# Supply__1.net
KiCad netlist of a schematic drawn in Altium Designer
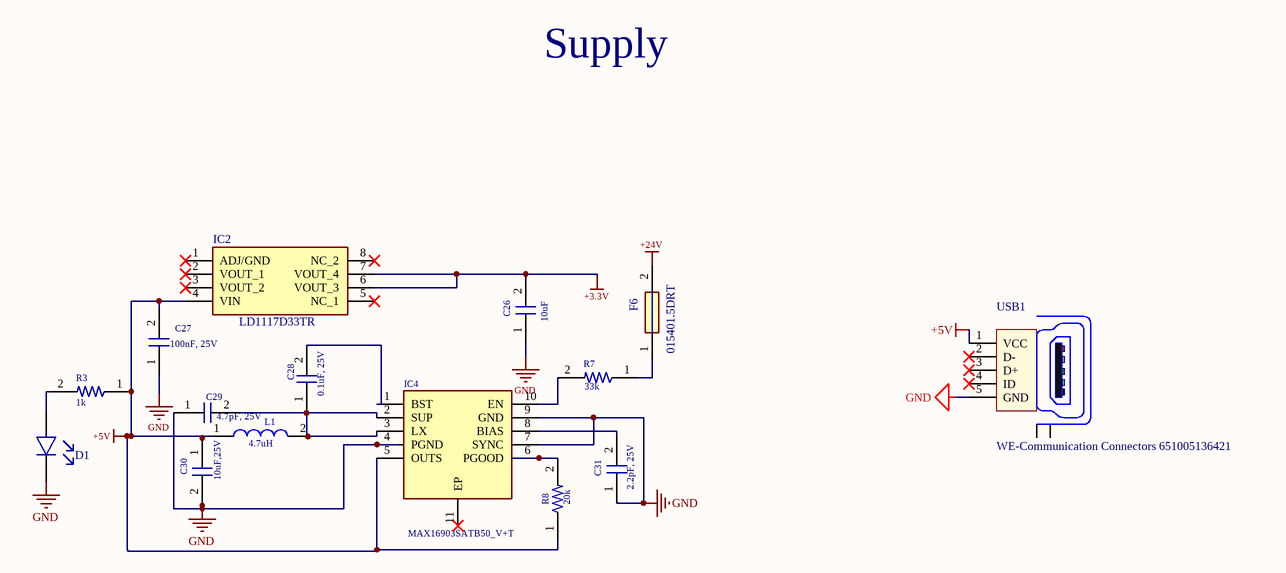
[diagram p0: Supply_ (1).SchDoc]

(export (version "E")
  (design (tool "Eeschema 10.0.6"))
  (components
    (comp (ref "C26")
      (value "10uF")
      (footprint "C 1206")
      (description "Condensador")
      (libsource (lib "MotoLibrary") (part "Condensador"))
    )
    (comp (ref "C27")
      (value "100nF, 25V")
      (footprint "C 1206")
      (description "Condensador")
      (libsource (lib "MotoLibrary") (part "Condensador"))
    )
    (comp (ref "C28")
      (value "0.1uF, 25V")
      (footprint "C 1206")
      (description "Condensador")
      (libsource (lib "MotoLibrary") (part "Condensador"))
    )
    (comp (ref "C29")
      (value "4.7pF, 25V")
      (footprint "C 1206")
      (description "Condensador")
      (libsource (lib "MotoLibrary") (part "Condensador"))
    )
    (comp (ref "C30")
      (value "10uF,25V")
      (footprint "C 1206")
      (description "Condensador")
      (libsource (lib "MotoLibrary") (part "Condensador"))
    )
    (comp (ref "C31")
      (value "2.2pF, 25V")
      (footprint "C 1206")
      (description "Condensador")
      (libsource (lib "MotoLibrary") (part "Condensador"))
    )
    (comp (ref "D1")
      (value "Valor")
      (footprint "LED 0805")
      (description "LED")
      (libsource (lib "MotoLibrary") (part "LED"))
    )
    (comp (ref "F6")
      (value "015401.5DRT")
      (footprint "Fuse Holder")
      (description "Fuse")
      (fields (field (name "MOUSER PART NUMBER") "576-015401.5DRT"))
      (libsource (lib "*") (part "015401.5DRT"))
    )
    (comp (ref "IC2")
      (value "LD1117D33TR")
      (footprint "SOIC127P600X175-8N")
      (description "Integrated Circuit")
      (fields (field (name "MOUSER PART NUMBER") "511-LD1117D33-TR"))
      (libsource (lib "*") (part "LD1117D33TR"))
    )
    (comp (ref "IC4")
      (value "MAX16903SATB50_V+T")
      (footprint "SON50P300X300X80-11N")
      (description "Integrated Circuit")
      (fields (field (name "MANUFACTURER_PART_NUMBER") "MAX16903SATB50/V+T"))
      (libsource (lib "*") (part "MAX16903SATB50_V+T"))
    )
    (comp (ref "L1")
      (value "4.7uH")
      (footprint "MPX1D0530L150")
      (description "Inductor")
      (libsource (lib "MotoLibrary") (part "Inductor"))
    )
    (comp (ref "R3")
      (value "1k")
      (footprint "R 0201")
      (description "Resistencia")
      (libsource (lib "MotoLibrary") (part "Resistencia"))
    )
    (comp (ref "R7")
      (value "33k")
      (footprint "R 0805")
      (description "Resistencia")
      (libsource (lib "MotoLibrary") (part "Resistencia"))
    )
    (comp (ref "R8")
      (value "20k")
      (footprint "R 0805")
      (description "Resistencia")
      (libsource (lib "MotoLibrary") (part "Resistencia"))
    )
    (comp (ref "USB1")
      (value "WE-Communication Connectors 651005136421")
      (footprint "65100516121")
      (description "WR-COM Mini USB Vertical TH Type B 5 Contacts")
      (fields
        (field (name "MANUFACTURER") "Würth Elektronik eiSos GmbH")
        (field (name "PARTNO") "651005136421")
        (field (name "CREATED BY") "Karrer Zheng")
      )
      (libsource (lib "651005136421_Altium_651005136421_rev16d") (part "WE-Communication Connectors 651005136421"))
    )
  )
  (nets
    (net (code "1") (name "+3.3V") (class "Default")
      (node (ref "C26") (pin "2") (pintype "passive"))
      (node (ref "IC2") (pin "6") (pinfunction "VOUT_3_6") (pintype "passive"))
      (node (ref "IC2") (pin "7") (pinfunction "VOUT_4_7") (pintype "passive"))
    )
    (net (code "2") (name "+5V") (class "Default")
      (node (ref "C27") (pin "2") (pintype "passive"))
      (node (ref "C30") (pin "1") (pintype "passive"))
      (node (ref "IC2") (pin "4") (pinfunction "VIN_4") (pintype "passive"))
      (node (ref "IC4") (pin "5") (pinfunction "OUTS_5") (pintype "passive"))
      (node (ref "L1") (pin "1") (pinfunction "1_1") (pintype "passive"))
      (node (ref "R3") (pin "1") (pinfunction "1_1") (pintype "passive"))
      (node (ref "R8") (pin "1") (pinfunction "1_1") (pintype "passive"))
      (node (ref "USB1") (pin "1") (pinfunction "VCC_1") (pintype "passive"))
    )
    (net (code "3") (name "+24V") (class "Default")
      (node (ref "F6") (pin "2") (pinfunction "2_2") (pintype "passive"))
    )
    (net (code "4") (name "GND") (class "Default")
      (node (ref "C26") (pin "1") (pintype "passive"))
      (node (ref "C27") (pin "1") (pintype "passive"))
      (node (ref "C29") (pin "1") (pintype "passive"))
      (node (ref "C30") (pin "2") (pintype "passive"))
      (node (ref "C31") (pin "1") (pintype "passive"))
      (node (ref "D1") (pin "1") (pinfunction "1_1") (pintype "passive"))
      (node (ref "IC4") (pin "4") (pinfunction "PGND_4") (pintype "passive"))
      (node (ref "IC4") (pin "7") (pinfunction "SYNC_7") (pintype "passive"))
      (node (ref "IC4") (pin "9") (pinfunction "GND_9") (pintype "passive"))
      (node (ref "USB1") (pin "5") (pinfunction "GND_5") (pintype "passive"))
    )
    (net (code "5") (name "Net-(D1-Pad2)") (class "Default")
      (node (ref "D1") (pin "2") (pinfunction "2_2") (pintype "passive"))
      (node (ref "R3") (pin "2") (pinfunction "2_2") (pintype "passive"))
    )
    (net (code "6") (name "Net-(F6-Pad1)") (class "Default")
      (node (ref "F6") (pin "1") (pinfunction "1_1") (pintype "passive"))
      (node (ref "R7") (pin "1") (pinfunction "1_1") (pintype "passive"))
    )
    (net (code "7") (name "Net-(IC4-BIAS)") (class "Default")
      (node (ref "C31") (pin "2") (pintype "passive"))
      (node (ref "IC4") (pin "8") (pinfunction "BIAS_8") (pintype "passive"))
    )
    (net (code "8") (name "Net-(IC4-BST)") (class "Default")
      (node (ref "C28") (pin "2") (pintype "passive"))
      (node (ref "IC4") (pin "1") (pinfunction "BST_1") (pintype "passive"))
    )
    (net (code "9") (name "Net-(IC4-EN)") (class "Default")
      (node (ref "IC4") (pin "10") (pinfunction "EN_10") (pintype "passive"))
      (node (ref "R7") (pin "2") (pinfunction "2_2") (pintype "passive"))
    )
    (net (code "10") (name "Net-(IC4-LX)") (class "Default")
      (node (ref "C28") (pin "1") (pintype "passive"))
      (node (ref "C29") (pin "2") (pintype "passive"))
      (node (ref "IC4") (pin "2") (pinfunction "SUP_2") (pintype "passive"))
      (node (ref "IC4") (pin "3") (pinfunction "LX_3") (pintype "passive"))
      (node (ref "L1") (pin "2") (pinfunction "2_2") (pintype "passive"))
    )
    (net (code "11") (name "Net-(IC4-PGOOD)") (class "Default")
      (node (ref "IC4") (pin "6") (pinfunction "PGOOD_6") (pintype "passive"))
      (node (ref "R8") (pin "2") (pinfunction "2_2") (pintype "passive"))
    )
    (net (code "12") (name "unconnected-(IC2-ADJ{slash}GND-Pad1)") (class "Default")
      (node (ref "IC2") (pin "1") (pinfunction "ADJ/GND_1") (pintype "passive+no_connect"))
    )
    (net (code "13") (name "unconnected-(IC2-NC_1-Pad5)") (class "Default")
      (node (ref "IC2") (pin "5") (pinfunction "NC_1_5") (pintype "passive+no_connect"))
    )
    (net (code "14") (name "unconnected-(IC2-NC_2-Pad8)") (class "Default")
      (node (ref "IC2") (pin "8") (pinfunction "NC_2_8") (pintype "passive+no_connect"))
    )
    (net (code "15") (name "unconnected-(IC2-VOUT_1-Pad2)") (class "Default")
      (node (ref "IC2") (pin "2") (pinfunction "VOUT_1_2") (pintype "passive+no_connect"))
    )
    (net (code "16") (name "unconnected-(IC2-VOUT_2-Pad3)") (class "Default")
      (node (ref "IC2") (pin "3") (pinfunction "VOUT_2_3") (pintype "passive+no_connect"))
    )
    (net (code "17") (name "unconnected-(IC4-EP-Pad11)") (class "Default")
      (node (ref "IC4") (pin "11") (pinfunction "EP_11") (pintype "passive+no_connect"))
    )
    (net (code "18") (name "unconnected-(USB1-D+-Pad3)") (class "Default")
      (node (ref "USB1") (pin "3") (pinfunction "D+_3") (pintype "passive+no_connect"))
    )
    (net (code "19") (name "unconnected-(USB1-D--Pad2)") (class "Default")
      (node (ref "USB1") (pin "2") (pinfunction "D-_2") (pintype "passive+no_connect"))
    )
    (net (code "20") (name "unconnected-(USB1-ID-Pad4)") (class "Default")
      (node (ref "USB1") (pin "4") (pinfunction "ID_4") (pintype "passive+no_connect"))
    )
    (net (code "21") (name "unconnected-(USB1-Shield-PadZ1)") (class "Default")
      (node (ref "USB1") (pin "Z1") (pinfunction "Shield_Z1") (pintype "passive"))
    )
    (net (code "22") (name "unconnected-(USB1-Shield-PadZ2)") (class "Default")
      (node (ref "USB1") (pin "Z2") (pinfunction "Shield_Z2") (pintype "passive"))
    )
  )
)
